# controller_board.net
KiCad netlist of a schematic drawn in EAGLE
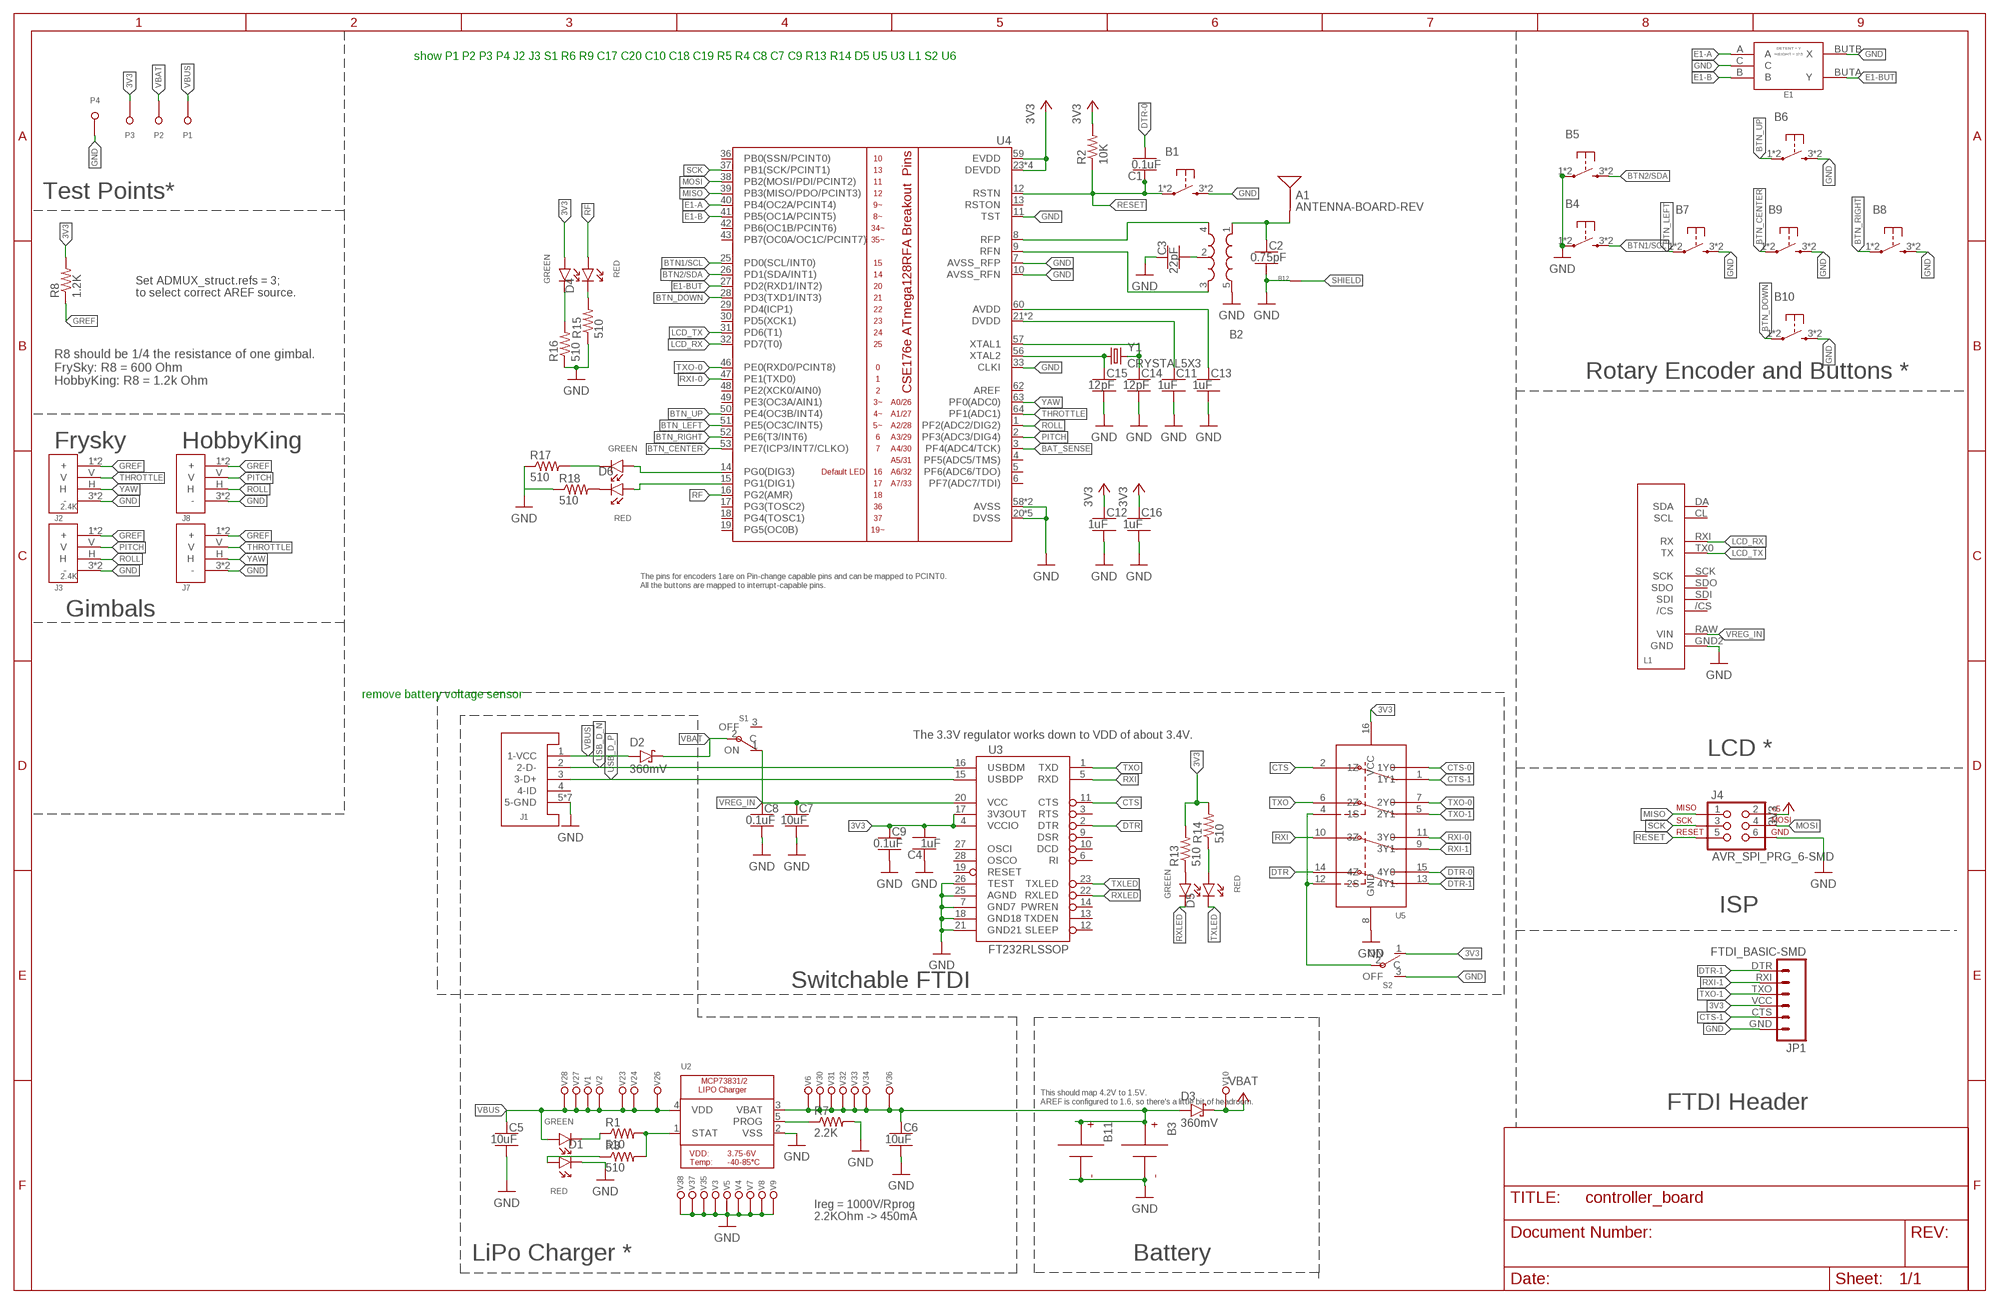
[diagram p0: schematic, sheet 1]

(export (version "E")
  (design (tool "Eeschema 10.0.6"))
  (components
    (comp (ref "A1")
      (value "ANTENNA-BOARD-REV")
      (footprint "eagle-import:ANT_PCB_2.4GHZ_NRF8001_1.6MM_1OZ_REV")
      (fields (field (name "CREATOR") "Swanson"))
      (libsource (lib "eagle-import") (part "ANTENNA-BOARD-REV"))
    )
    (comp (ref "B1")
      (value "PUSHBUTTON_-4.5X4.5")
      (footprint "eagle-import:4.5MM_TACTILE_SWITCH_TL3305AF160QG")
      (fields (field (name "CREATOR") "Swanson"))
      (libsource (lib "eagle-import") (part "PUSHBUTTON_-4.5X4.5"))
    )
    (comp (ref "B2")
      (value "BALUN0805")
      (footprint "eagle-import:BALUN")
      (fields
        (field (name "MFR") "Wurth Electronics Inc")
        (field (name "MPN") "748421245")
        (field (name "CREATOR") "Swanson")
        (field (name "REVIEWER") "Swanson")
      )
      (libsource (lib "eagle-import") (part "BALUN0805"))
    )
    (comp (ref "B3")
      (value "BATTERY-SPRING-SMD")
      (footprint "eagle-import:WIRE-TERMINAL-1X2-2.5MM-SMD-AVX-009276002021106")
      (libsource (lib "eagle-import") (part "BATTERY-SPRING-SMD"))
    )
    (comp (ref "B4")
      (value "PUSHBUTTON_-4.5X4.5")
      (footprint "eagle-import:4.5MM_TACTILE_SWITCH_TL3305AF160QG")
      (fields (field (name "CREATOR") "Swanson"))
      (libsource (lib "eagle-import") (part "PUSHBUTTON_-4.5X4.5"))
    )
    (comp (ref "B5")
      (value "PUSHBUTTON_-4.5X4.5")
      (footprint "eagle-import:4.5MM_TACTILE_SWITCH_TL3305AF160QG")
      (fields (field (name "CREATOR") "Swanson"))
      (libsource (lib "eagle-import") (part "PUSHBUTTON_-4.5X4.5"))
    )
    (comp (ref "B6")
      (value "PUSHBUTTON_-4.5X4.5")
      (footprint "eagle-import:4.5MM_TACTILE_SWITCH_TL3305AF160QG")
      (fields (field (name "CREATOR") "Swanson"))
      (libsource (lib "eagle-import") (part "PUSHBUTTON_-4.5X4.5"))
    )
    (comp (ref "B7")
      (value "PUSHBUTTON_-4.5X4.5")
      (footprint "eagle-import:4.5MM_TACTILE_SWITCH_TL3305AF160QG")
      (fields (field (name "CREATOR") "Swanson"))
      (libsource (lib "eagle-import") (part "PUSHBUTTON_-4.5X4.5"))
    )
    (comp (ref "B8")
      (value "PUSHBUTTON_-4.5X4.5")
      (footprint "eagle-import:4.5MM_TACTILE_SWITCH_TL3305AF160QG")
      (fields (field (name "CREATOR") "Swanson"))
      (libsource (lib "eagle-import") (part "PUSHBUTTON_-4.5X4.5"))
    )
    (comp (ref "B9")
      (value "PUSHBUTTON_-4.5X4.5")
      (footprint "eagle-import:4.5MM_TACTILE_SWITCH_TL3305AF160QG")
      (fields (field (name "CREATOR") "Swanson"))
      (libsource (lib "eagle-import") (part "PUSHBUTTON_-4.5X4.5"))
    )
    (comp (ref "B10")
      (value "PUSHBUTTON_-4.5X4.5")
      (footprint "eagle-import:4.5MM_TACTILE_SWITCH_TL3305AF160QG")
      (fields (field (name "CREATOR") "Swanson"))
      (libsource (lib "eagle-import") (part "PUSHBUTTON_-4.5X4.5"))
    )
    (comp (ref "B11")
      (value "BATTERY-SCREW-TERMINAL")
      (footprint "eagle-import:SCREW-TERMINAL-1X2-2.54MM")
      (fields (field (name "CREATOR") "Swanson"))
      (libsource (lib "eagle-import") (part "BATTERY-SCREW-TERMINAL"))
    )
    (comp (ref "B12")
      (value "NET_BRIDGE")
      (footprint "eagle-import:NET_BRIDGE")
      (fields (field (name "CREATOR") "Michael Gonzalez"))
      (libsource (lib "eagle-import") (part "NET_BRIDGE"))
    )
    (comp (ref "C1")
      (value "0.1uF")
      (footprint "eagle-import:CAPC2012X140_HS")
      (fields
        (field (name "MFR") "TDK")
        (field (name "MPN") "C2012X7R2A104K125AA")
        (field (name "CREATOR") "Swanson")
        (field (name "REVIEWER") "Swanson")
      )
      (libsource (lib "eagle-import") (part "CAPACITOR-NP_SMD-2012-0805_CERAMIC-0.1UF"))
    )
    (comp (ref "C2")
      (value "0.75pF")
      (footprint "eagle-import:CAPC2012X140_HS")
      (fields
        (field (name "MFR") "Murata Electronics North America")
        (field (name "MPN") "GQM2195C2AR75CB01D")
        (field (name "CREATOR") "Swanson")
        (field (name "REVIEWER") "Swanson")
      )
      (libsource (lib "eagle-import") (part "CAPACITOR-NP_SMD-2012-0805_CERAMIC-0.75PF"))
    )
    (comp (ref "C3")
      (value "22pF")
      (footprint "eagle-import:CAPC2012X140_HS")
      (fields
        (field (name "MFR") "Murata Electronics North America")
        (field (name "MPN") "GRM21A5C2E220JW01D")
        (field (name "CREATOR") "Swanson")
        (field (name "REVIEWER") "Swanson")
      )
      (libsource (lib "eagle-import") (part "CAPACITOR-NP_SMD-2012-0805_CERAMIC-22PF"))
    )
    (comp (ref "C4")
      (value "1uF")
      (footprint "eagle-import:CAPC2012X140_HS")
      (fields
        (field (name "MFR") "Taiyo Yuden")
        (field (name "MPN") "TMK212B7105KG-T")
        (field (name "CREATOR") "Swanson")
        (field (name "REVIEWER") "Swanson")
      )
      (libsource (lib "eagle-import") (part "CAPACITOR-NP_SMD-2012-0805_CERAMIC-1UF"))
    )
    (comp (ref "C5")
      (value "10uF")
      (footprint "eagle-import:CAPC2012X140_HS")
      (fields (field (name "CREATOR") "Swanson") (field (name "REVIEWER") "Swanson"))
      (libsource (lib "eagle-import") (part "CAPACITOR-NP_SMD-2012-0805_CERAMIC-10UF"))
    )
    (comp (ref "C6")
      (value "10uF")
      (footprint "eagle-import:CAPC2012X140_HS")
      (fields (field (name "CREATOR") "Swanson") (field (name "REVIEWER") "Swanson"))
      (libsource (lib "eagle-import") (part "CAPACITOR-NP_SMD-2012-0805_CERAMIC-10UF"))
    )
    (comp (ref "C7")
      (value "10uF")
      (footprint "eagle-import:CAPC2012X140_HS")
      (fields (field (name "CREATOR") "Swanson") (field (name "REVIEWER") "Swanson"))
      (libsource (lib "eagle-import") (part "CAPACITOR-NP_SMD-2012-0805_CERAMIC-10UF"))
    )
    (comp (ref "C8")
      (value "0.1uF")
      (footprint "eagle-import:CAPC2012X140_HS")
      (fields
        (field (name "MFR") "TDK")
        (field (name "MPN") "C2012X7R2A104K125AA")
        (field (name "CREATOR") "Swanson")
        (field (name "REVIEWER") "Swanson")
      )
      (libsource (lib "eagle-import") (part "CAPACITOR-NP_SMD-2012-0805_CERAMIC-0.1UF"))
    )
    (comp (ref "C9")
      (value "0.1uF")
      (footprint "eagle-import:CAPC2012X140_HS")
      (fields
        (field (name "MFR") "TDK")
        (field (name "MPN") "C2012X7R2A104K125AA")
        (field (name "CREATOR") "Swanson")
        (field (name "REVIEWER") "Swanson")
      )
      (libsource (lib "eagle-import") (part "CAPACITOR-NP_SMD-2012-0805_CERAMIC-0.1UF"))
    )
    (comp (ref "C11")
      (value "1uF")
      (footprint "eagle-import:CAPC2012X140_HS")
      (fields
        (field (name "MFR") "Taiyo Yuden")
        (field (name "MPN") "TMK212B7105KG-T")
        (field (name "CREATOR") "Swanson")
        (field (name "REVIEWER") "Swanson")
      )
      (libsource (lib "eagle-import") (part "CAPACITOR-NP_SMD-2012-0805_CERAMIC-1UF"))
    )
    (comp (ref "C12")
      (value "1uF")
      (footprint "eagle-import:CAPC2012X140_HS")
      (fields
        (field (name "MFR") "Taiyo Yuden")
        (field (name "MPN") "TMK212B7105KG-T")
        (field (name "CREATOR") "Swanson")
        (field (name "REVIEWER") "Swanson")
      )
      (libsource (lib "eagle-import") (part "CAPACITOR-NP_SMD-2012-0805_CERAMIC-1UF"))
    )
    (comp (ref "C13")
      (value "1uF")
      (footprint "eagle-import:CAPC2012X140_HS")
      (fields
        (field (name "MFR") "Taiyo Yuden")
        (field (name "MPN") "TMK212B7105KG-T")
        (field (name "CREATOR") "Swanson")
        (field (name "REVIEWER") "Swanson")
      )
      (libsource (lib "eagle-import") (part "CAPACITOR-NP_SMD-2012-0805_CERAMIC-1UF"))
    )
    (comp (ref "C14")
      (value "12pF")
      (footprint "eagle-import:CAPC2012X140_HS")
      (fields
        (field (name "MFR") "Murata Electronics North America")
        (field (name "MPN") "GRM21A5C2E120JW01D")
        (field (name "CREATOR") "Swanson")
        (field (name "REVIEWER") "Swanson")
      )
      (libsource (lib "eagle-import") (part "CAPACITOR-NP_SMD-2012-0805_CERAMIC-12PF"))
    )
    (comp (ref "C15")
      (value "12pF")
      (footprint "eagle-import:CAPC2012X140_HS")
      (fields
        (field (name "MFR") "Murata Electronics North America")
        (field (name "MPN") "GRM21A5C2E120JW01D")
        (field (name "CREATOR") "Swanson")
        (field (name "REVIEWER") "Swanson")
      )
      (libsource (lib "eagle-import") (part "CAPACITOR-NP_SMD-2012-0805_CERAMIC-12PF"))
    )
    (comp (ref "C16")
      (value "1uF")
      (footprint "eagle-import:CAPC2012X140_HS")
      (fields
        (field (name "MFR") "Taiyo Yuden")
        (field (name "MPN") "TMK212B7105KG-T")
        (field (name "CREATOR") "Swanson")
        (field (name "REVIEWER") "Swanson")
      )
      (libsource (lib "eagle-import") (part "CAPACITOR-NP_SMD-2012-0805_CERAMIC-1UF"))
    )
    (comp (ref "D1")
      (value "LED-2X-GREEN/RED")
      (footprint "eagle-import:LED-2X-LTST-C155")
      (fields
        (field (name "COLOR2") "RED")
        (field (name "COLOR1") "GREEN")
        (field (name "CREATOR") "Swanson")
      )
      (libsource (lib "eagle-import") (part "LED-2X-GREEN/RED"))
    )
    (comp (ref "D2")
      (value "360mV")
      (footprint "eagle-import:SOD3716X135_HS")
      (fields
        (field (name "MFR") "Toshiba Semiconductor and Storage")
        (field (name "MPN") "CRS08(TE85L,Q,M)")
        (field (name "CREATOR") "Swanson")
        (field (name "REVIEWER") "Swanson")
      )
      (libsource (lib "eagle-import") (part "DIODE-SCHOTTKY_SMD-SOD123-360MV"))
    )
    (comp (ref "D3")
      (value "360mV")
      (footprint "eagle-import:SOD3716X135_HS")
      (fields
        (field (name "MFR") "Toshiba Semiconductor and Storage")
        (field (name "MPN") "CRS08(TE85L,Q,M)")
        (field (name "CREATOR") "Swanson")
        (field (name "REVIEWER") "Swanson")
      )
      (libsource (lib "eagle-import") (part "DIODE-SCHOTTKY_SMD-SOD123-360MV"))
    )
    (comp (ref "D4")
      (value "LED-2X-GREEN/RED")
      (footprint "eagle-import:LED-2X-LTST-C155")
      (fields
        (field (name "COLOR2") "RED")
        (field (name "COLOR1") "GREEN")
        (field (name "CREATOR") "Swanson")
      )
      (libsource (lib "eagle-import") (part "LED-2X-GREEN/RED"))
    )
    (comp (ref "D5")
      (value "LED-2X-GREEN/RED")
      (footprint "eagle-import:LED-2X-LTST-C155")
      (fields
        (field (name "COLOR2") "RED")
        (field (name "COLOR1") "GREEN")
        (field (name "CREATOR") "Swanson")
      )
      (libsource (lib "eagle-import") (part "LED-2X-GREEN/RED"))
    )
    (comp (ref "D6")
      (value "LED-2X-GREEN/RED")
      (footprint "eagle-import:LED-2X-LTST-C155")
      (fields
        (field (name "COLOR2") "RED")
        (field (name "COLOR1") "GREEN")
        (field (name "CREATOR") "Swanson")
      )
      (libsource (lib "eagle-import") (part "LED-2X-GREEN/RED"))
    )
    (comp (ref "E1")
      (value "ROTARY-ENCODER-W/BUTTON-BOURNS-PEC12R-4217F")
      (footprint "eagle-import:BOURNS-PEC12R")
      (fields (field (name "DETENT") "Y") (field (name "HEIGHT") "17.5") (field (name "CREATOR") "Swanson"))
      (libsource (lib "eagle-import") (part "ROTARY-ENCODER-W/BUTTON-BOURNS-PEC12R-4217F"))
    )
    (comp (ref "J1")
      (value "USB-MICROA-AMPHENOL-10118192-0001LF")
      (footprint "eagle-import:USB-MICROA-10118192-0001LF")
      (fields (field (name "CREATOR") "Swanson"))
      (libsource (lib "eagle-import") (part "USB-MICROA-AMPHENOL-10118192-0001LF"))
    )
    (comp (ref "J2")
      (value "2.4K")
      (footprint "eagle-import:JST-13-PTH")
      (fields (field (name "CREATOR") "Swanson"))
      (libsource (lib "eagle-import") (part "FRSKY-GIMBAL-FRYSKY"))
    )
    (comp (ref "J3")
      (value "2.4K")
      (footprint "eagle-import:JST-13-PTH")
      (fields (field (name "SPICEPREFIX") "E") (field (name "CREATOR") "Swanson"))
      (libsource (lib "eagle-import") (part "FRSKY-GIMBAL-FRYSKY"))
    )
    (comp (ref "J4")
      (value "AVR_SPI_PRG_6-SMD")
      (footprint "eagle-import:2X3-SMD")
      (fields (field (name "CREATOR") "Swanson"))
      (libsource (lib "eagle-import") (part "AVR_SPI_PRG_6-SMD"))
    )
    (comp (ref "J7")
      (value "FRSKY-GIMBAL-2X-SERVO-SMD")
      (footprint "eagle-import:2X-SERVO-SMD")
      (libsource (lib "eagle-import") (part "FRSKY-GIMBAL-2X-SERVO-SMD"))
    )
    (comp (ref "J8")
      (value "FRSKY-GIMBAL-2X-SERVO-SMD")
      (footprint "eagle-import:2X-SERVO-SMD")
      (libsource (lib "eagle-import") (part "FRSKY-GIMBAL-2X-SERVO-SMD"))
    )
    (comp (ref "JP1")
      (value "FTDI_BASIC-SMD")
      (footprint "eagle-import:FTDI-BASIC-SMD")
      (libsource (lib "eagle-import") (part "FTDI_BASIC-SMD"))
    )
    (comp (ref "L1")
      (value "SPARKFUN_SERLCD_SERIAL_REDUCED-SMD")
      (footprint "eagle-import:SPARKFUN_SERLCD_16X2_REDUCED_SMD")
      (fields (field (name "CREATOR") "Swanson"))
      (libsource (lib "eagle-import") (part "SPARKFUN_SERLCD_SERIAL_REDUCED-SMD"))
    )
    (comp (ref "P1")
      (value "TEST-POINT")
      (footprint "eagle-import:TEST-POINT-KEYSTONE-5000")
      (fields (field (name "CREATOR") "Swanson"))
      (libsource (lib "eagle-import") (part "TEST-POINT"))
    )
    (comp (ref "P2")
      (value "TEST-POINT")
      (footprint "eagle-import:TEST-POINT-KEYSTONE-5000")
      (fields (field (name "CREATOR") "Swanson"))
      (libsource (lib "eagle-import") (part "TEST-POINT"))
    )
    (comp (ref "P3")
      (value "TEST-POINT")
      (footprint "eagle-import:TEST-POINT-KEYSTONE-5000")
      (fields (field (name "CREATOR") "Swanson"))
      (libsource (lib "eagle-import") (part "TEST-POINT"))
    )
    (comp (ref "P4")
      (value "TEST-POINT")
      (footprint "eagle-import:TEST-POINT-KEYSTONE-5000")
      (fields (field (name "CREATOR") "Swanson"))
      (libsource (lib "eagle-import") (part "TEST-POINT"))
    )
    (comp (ref "R1")
      (value "510")
      (footprint "eagle-import:RESC2012X60_HS")
      (fields (field (name "CREATOR") "SWANSON"))
      (libsource (lib "eagle-import") (part "RESISTOR_SMD-2012-0805-510"))
    )
    (comp (ref "R2")
      (value "10K")
      (footprint "eagle-import:RESC2012X60_HS")
      (fields
        (field (name "MFR") "Yageo")
        (field (name "MPN") "RC0805JR-0710KL")
        (field (name "CREATOR") "Swanson")
        (field (name "REVIEWER") "Swanson")
      )
      (libsource (lib "eagle-import") (part "RESISTOR_SMD-2012-0805-10K"))
    )
    (comp (ref "R3")
      (value "510")
      (footprint "eagle-import:RESC2012X60_HS")
      (fields (field (name "CREATOR") "SWANSON"))
      (libsource (lib "eagle-import") (part "RESISTOR_SMD-2012-0805-510"))
    )
    (comp (ref "R7")
      (value "2.2K")
      (footprint "eagle-import:RESC2012X60_HS")
      (fields (field (name "CREATOR") "SWANSON"))
      (libsource (lib "eagle-import") (part "RESISTOR_SMD-2012-0805-2.2K"))
    )
    (comp (ref "R8")
      (value "1.2K")
      (footprint "eagle-import:RESC2012X60_HS")
      (fields (field (name "CREATOR") "Swanson"))
      (libsource (lib "eagle-import") (part "RESISTOR_SMD-2012-0805-1.2K"))
    )
    (comp (ref "R13")
      (value "510")
      (footprint "eagle-import:RESC2012X60_HS")
      (fields (field (name "CREATOR") "SWANSON"))
      (libsource (lib "eagle-import") (part "RESISTOR_SMD-2012-0805-510"))
    )
    (comp (ref "R14")
      (value "510")
      (footprint "eagle-import:RESC2012X60_HS")
      (fields (field (name "CREATOR") "SWANSON"))
      (libsource (lib "eagle-import") (part "RESISTOR_SMD-2012-0805-510"))
    )
    (comp (ref "R15")
      (value "510")
      (footprint "eagle-import:RESC2012X60_HS")
      (fields (field (name "CREATOR") "SWANSON"))
      (libsource (lib "eagle-import") (part "RESISTOR_SMD-2012-0805-510"))
    )
    (comp (ref "R16")
      (value "510")
      (footprint "eagle-import:RESC2012X60_HS")
      (fields (field (name "CREATOR") "SWANSON"))
      (libsource (lib "eagle-import") (part "RESISTOR_SMD-2012-0805-510"))
    )
    (comp (ref "R17")
      (value "510")
      (footprint "eagle-import:RESC2012X60_HS")
      (fields (field (name "CREATOR") "SWANSON"))
      (libsource (lib "eagle-import") (part "RESISTOR_SMD-2012-0805-510"))
    )
    (comp (ref "R18")
      (value "510")
      (footprint "eagle-import:RESC2012X60_HS")
      (fields (field (name "CREATOR") "SWANSON"))
      (libsource (lib "eagle-import") (part "RESISTOR_SMD-2012-0805-510"))
    )
    (comp (ref "S1")
      (value "POWER-SWITCH-MFS201N-9-Z-SMD-VERTICAL")
      (footprint "eagle-import:JS102011JCQN")
      (fields (field (name "CREATOR") "Swanson"))
      (libsource (lib "eagle-import") (part "POWER-SWITCH-MFS201N-9-Z-SMD-VERTICAL"))
    )
    (comp (ref "S2")
      (value "POWER-SWITCH-MFS201N-9-Z-SMD-VERTICAL")
      (footprint "eagle-import:JS102011JCQN")
      (fields (field (name "CREATOR") "Swanson"))
      (libsource (lib "eagle-import") (part "POWER-SWITCH-MFS201N-9-Z-SMD-VERTICAL"))
    )
    (comp (ref "U2")
      (value "MCP73831T-2ACI/OT")
      (footprint "eagle-import:SOT23-5")
      (fields (field (name "CREATOR") "Adafruit"))
      (libsource (lib "eagle-import") (part "MCP73831/2"))
    )
    (comp (ref "U3")
      (value "FT232RLSSOP")
      (footprint "eagle-import:SSOP28DB")
      (fields (field (name "CREATOR") "Swanson"))
      (libsource (lib "eagle-import") (part "FT232RLSSOP"))
    )
    (comp (ref "U4")
      (value "ATMEGA128RFA1")
      (footprint "eagle-import:QFN-64")
      (fields
        (field (name "MFR") "Atmel")
        (field (name "MPN") "ATMEGA128RFA1-ZUR00")
        (field (name "CREATOR") "Swanson")
        (field (name "REVIEWER") "Swanson")
      )
      (libsource (lib "eagle-import") (part "ATMEGA128RFA1"))
    )
    (comp (ref "U5")
      (value "DPDT-X2")
      (footprint "eagle-import:SOP65P640X110-16")
      (fields (field (name "CREATOR") "Swanson"))
      (libsource (lib "eagle-import") (part "DPDT-X2"))
    )
    (comp (ref "V1")
      (value "LOCKED-VIA-0.2")
      (footprint "eagle-import:VIA-0.2MM")
      (fields (field (name "CREATOR") "Swanson"))
      (libsource (lib "eagle-import") (part "LOCKED-VIA-0.2"))
    )
    (comp (ref "V2")
      (value "LOCKED-VIA-0.2")
      (footprint "eagle-import:VIA-0.2MM")
      (fields (field (name "CREATOR") "Swanson"))
      (libsource (lib "eagle-import") (part "LOCKED-VIA-0.2"))
    )
    (comp (ref "V3")
      (value "LOCKED-VIA-0.2")
      (footprint "eagle-import:VIA-0.2MM")
      (fields (field (name "CREATOR") "Swanson"))
      (libsource (lib "eagle-import") (part "LOCKED-VIA-0.2"))
    )
    (comp (ref "V4")
      (value "LOCKED-VIA-0.2")
      (footprint "eagle-import:VIA-0.2MM")
      (fields (field (name "CREATOR") "Swanson"))
      (libsource (lib "eagle-import") (part "LOCKED-VIA-0.2"))
    )
    (comp (ref "V5")
      (value "LOCKED-VIA-0.2")
      (footprint "eagle-import:VIA-0.2MM")
      (fields (field (name "CREATOR") "Swanson"))
      (libsource (lib "eagle-import") (part "LOCKED-VIA-0.2"))
    )
    (comp (ref "V6")
      (value "LOCKED-VIA-0.2")
      (footprint "eagle-import:VIA-0.2MM")
      (fields (field (name "CREATOR") "Swanson"))
      (libsource (lib "eagle-import") (part "LOCKED-VIA-0.2"))
    )
    (comp (ref "V7")
      (value "LOCKED-VIA-0.2")
      (footprint "eagle-import:VIA-0.2MM")
      (fields (field (name "CREATOR") "Swanson"))
      (libsource (lib "eagle-import") (part "LOCKED-VIA-0.2"))
    )
    (comp (ref "V8")
      (value "LOCKED-VIA-0.2")
      (footprint "eagle-import:VIA-0.2MM")
      (fields (field (name "CREATOR") "Swanson"))
      (libsource (lib "eagle-import") (part "LOCKED-VIA-0.2"))
    )
    (comp (ref "V9")
      (value "LOCKED-VIA-0.2")
      (footprint "eagle-import:VIA-0.2MM")
      (fields (field (name "CREATOR") "Swanson"))
      (libsource (lib "eagle-import") (part "LOCKED-VIA-0.2"))
    )
    (comp (ref "V10")
      (value "LOCKED-VIA-0.2")
      (footprint "eagle-import:VIA-0.2MM")
      (fields (field (name "CREATOR") "Swanson"))
      (libsource (lib "eagle-import") (part "LOCKED-VIA-0.2"))
    )
    (comp (ref "V23")
      (value "LOCKED-VIA-0.2")
      (footprint "eagle-import:VIA-0.2MM")
      (fields (field (name "CREATOR") "Swanson"))
      (libsource (lib "eagle-import") (part "LOCKED-VIA-0.2"))
    )
    (comp (ref "V24")
      (value "LOCKED-VIA-0.2")
      (footprint "eagle-import:VIA-0.2MM")
      (fields (field (name "CREATOR") "Swanson"))
      (libsource (lib "eagle-import") (part "LOCKED-VIA-0.2"))
    )
    (comp (ref "V26")
      (value "LOCKED-VIA-0.2")
      (footprint "eagle-import:VIA-0.2MM")
      (fields (field (name "CREATOR") "Swanson"))
      (libsource (lib "eagle-import") (part "LOCKED-VIA-0.2"))
    )
    (comp (ref "V27")
      (value "LOCKED-VIA-0.2")
      (footprint "eagle-import:VIA-0.2MM")
      (fields (field (name "CREATOR") "Swanson"))
      (libsource (lib "eagle-import") (part "LOCKED-VIA-0.2"))
    )
    (comp (ref "V28")
      (value "LOCKED-VIA-0.2")
      (footprint "eagle-import:VIA-0.2MM")
      (fields (field (name "CREATOR") "Swanson"))
      (libsource (lib "eagle-import") (part "LOCKED-VIA-0.2"))
    )
    (comp (ref "V30")
      (value "LOCKED-VIA-0.2")
      (footprint "eagle-import:VIA-0.2MM")
      (fields (field (name "CREATOR") "Swanson"))
      (libsource (lib "eagle-import") (part "LOCKED-VIA-0.2"))
    )
    (comp (ref "V31")
      (value "LOCKED-VIA-0.2")
      (footprint "eagle-import:VIA-0.2MM")
      (fields (field (name "CREATOR") "Swanson"))
      (libsource (lib "eagle-import") (part "LOCKED-VIA-0.2"))
    )
    (comp (ref "V32")
      (value "LOCKED-VIA-0.2")
      (footprint "eagle-import:VIA-0.2MM")
      (fields (field (name "CREATOR") "Swanson"))
      (libsource (lib "eagle-import") (part "LOCKED-VIA-0.2"))
    )
    (comp (ref "V33")
      (value "LOCKED-VIA-0.2")
      (footprint "eagle-import:VIA-0.2MM")
      (fields (field (name "CREATOR") "Swanson"))
      (libsource (lib "eagle-import") (part "LOCKED-VIA-0.2"))
    )
    (comp (ref "V34")
      (value "LOCKED-VIA-0.2")
      (footprint "eagle-import:VIA-0.2MM")
      (fields (field (name "CREATOR") "Swanson"))
      (libsource (lib "eagle-import") (part "LOCKED-VIA-0.2"))
    )
    (comp (ref "V35")
      (value "LOCKED-VIA-0.2")
      (footprint "eagle-import:VIA-0.2MM")
      (fields (field (name "CREATOR") "Swanson"))
      (libsource (lib "eagle-import") (part "LOCKED-VIA-0.2"))
    )
    (comp (ref "V36")
      (value "LOCKED-VIA-0.2")
      (footprint "eagle-import:VIA-0.2MM")
      (fields (field (name "CREATOR") "Swanson"))
      (libsource (lib "eagle-import") (part "LOCKED-VIA-0.2"))
    )
    (comp (ref "V37")
      (value "LOCKED-VIA-0.2")
      (footprint "eagle-import:VIA-0.2MM")
      (fields (field (name "CREATOR") "Swanson"))
      (libsource (lib "eagle-import") (part "LOCKED-VIA-0.2"))
    )
    (comp (ref "V38")
      (value "LOCKED-VIA-0.2")
      (footprint "eagle-import:VIA-0.2MM")
      (fields (field (name "CREATOR") "Swanson"))
      (libsource (lib "eagle-import") (part "LOCKED-VIA-0.2"))
    )
    (comp (ref "Y1")
      (value "CRYSTAL5X3")
      (footprint "eagle-import:CRYSTAL-SMD-5X3")
      (fields
        (field (name "MFR") "Abracon LLC")
        (field (name "MPN") "ABM3B-16.000MHZ-B2-T")
        (field (name "CREATOR") "Swanson")
        (field (name "REVIEWER") "Swanson")
      )
      (libsource (lib "eagle-import") (part "CRYSTAL5X3"))
    )
  )
  (nets
    (net (code "1") (name "3V3") (class "Default")
      (node (ref "C12") (pin "1") (pinfunction "1_1") (pintype "passive"))
      (node (ref "C16") (pin "1") (pinfunction "1_1") (pintype "passive"))
      (node (ref "C4") (pin "2") (pinfunction "2_2") (pintype "passive"))
      (node (ref "C9") (pin "1") (pinfunction "1_1") (pintype "passive"))
      (node (ref "D4") (pin "A2") (pinfunction "A2_A2") (pintype "passive"))
      (node (ref "J4") (pin "2") (pinfunction "2_2") (pintype "passive"))
      (node (ref "JP1") (pin "VCC") (pinfunction "4_VCC") (pintype "passive"))
      (node (ref "P3") (pin "T") (pinfunction "T_T") (pintype "bidirectional"))
      (node (ref "R13") (pin "2") (pinfunction "2_2") (pintype "passive"))
      (node (ref "R14") (pin "2") (pinfunction "2_2") (pintype "passive"))
      (node (ref "R2") (pin "2") (pinfunction "2_2") (pintype "passive"))
      (node (ref "R8") (pin "2") (pinfunction "2_2") (pintype "passive"))
      (node (ref "S2") (pin "1") (pinfunction "ON_1") (pintype "bidirectional"))
      (node (ref "U3") (pin "17") (pinfunction "3V3OUT_17") (pintype "output"))
      (node (ref "U3") (pin "4") (pinfunction "VCCIO_4") (pintype "power_in"))
      (node (ref "U4") (pin "23") (pinfunction "DEVDD_23") (pintype "bidirectional"))
      (node (ref "U4") (pin "34") (pinfunction "DEVDD_34") (pintype "bidirectional"))
      (node (ref "U4") (pin "44") (pinfunction "DEVDD_44") (pintype "bidirectional"))
      (node (ref "U4") (pin "54") (pinfunction "DEVDD_54") (pintype "bidirectional"))
      (node (ref "U4") (pin "59") (pinfunction "EVDD_59") (pintype "bidirectional"))
      (node (ref "U5") (pin "16") (pinfunction "VCC_16") (pintype "bidirectional"))
    )
    (net (code "2") (name "BAT_SENSE") (class "Default")
      (node (ref "U4") (pin "3") (pinfunction "PF4(ADC4/TCK)_3") (pintype "bidirectional"))
    )
    (net (code "3") (name "BTN1{slash}SCL") (class "Default")
      (node (ref "B4") (pin "3") (pinfunction "2_3") (pintype "passive"))
      (node (ref "B4") (pin "4") (pinfunction "2_4") (pintype "passive"))
      (node (ref "U4") (pin "25") (pinfunction "PD0(SCL/INT0)_25") (pintype "bidirectional"))
    )
    (net (code "4") (name "BTN2{slash}SDA") (class "Default")
      (node (ref "B5") (pin "3") (pinfunction "2_3") (pintype "passive"))
      (node (ref "B5") (pin "4") (pinfunction "2_4") (pintype "passive"))
      (node (ref "U4") (pin "26") (pinfunction "PD1(SDA/INT1)_26") (pintype "bidirectional"))
    )
    (net (code "5") (name "BTN_CENTER") (class "Default")
      (node (ref "B9") (pin "1") (pinfunction "1_1") (pintype "passive"))
      (node (ref "B9") (pin "2") (pinfunction "1_2") (pintype "passive"))
      (node (ref "U4") (pin "53") (pinfunction "PE7(ICP3/INT7/CLKO)_53") (pintype "bidirectional"))
    )
    (net (code "6") (name "BTN_DOWN") (class "Default")
      (node (ref "B10") (pin "1") (pinfunction "1_1") (pintype "passive"))
      (node (ref "B10") (pin "2") (pinfunction "1_2") (pintype "passive"))
      (node (ref "U4") (pin "28") (pinfunction "PD3(TXD1/INT3)_28") (pintype "bidirectional"))
    )
    (net (code "7") (name "BTN_LEFT") (class "Default")
      (node (ref "B7") (pin "1") (pinfunction "1_1") (pintype "passive"))
      (node (ref "B7") (pin "2") (pinfunction "1_2") (pintype "passive"))
      (node (ref "U4") (pin "51") (pinfunction "PE5(OC3C/INT5)_51") (pintype "bidirectional"))
    )
    (net (code "8") (name "BTN_RIGHT") (class "Default")
      (node (ref "B8") (pin "1") (pinfunction "1_1") (pintype "passive"))
      (node (ref "B8") (pin "2") (pinfunction "1_2") (pintype "passive"))
      (node (ref "U4") (pin "52") (pinfunction "PE6(T3/INT6)_52") (pintype "bidirectional"))
    )
    (net (code "9") (name "BTN_UP") (class "Default")
      (node (ref "B6") (pin "1") (pinfunction "1_1") (pintype "passive"))
      (node (ref "B6") (pin "2") (pinfunction "1_2") (pintype "passive"))
      (node (ref "U4") (pin "50") (pinfunction "PE4(OC3B/INT4)_50") (pintype "bidirectional"))
    )
    (net (code "10") (name "CTS") (class "Default")
      (node (ref "U3") (pin "11") (pinfunction "CTS_11") (pintype "input"))
      (node (ref "U5") (pin "2") (pinfunction "1Z_2") (pintype "bidirectional"))
    )
    (net (code "11") (name "CTS-0") (class "Default")
      (node (ref "U5") (pin "3") (pinfunction "1Y0_3") (pintype "bidirectional"))
    )
    (net (code "12") (name "CTS-1") (class "Default")
      (node (ref "JP1") (pin "CTS") (pinfunction "5_CTS") (pintype "passive"))
      (node (ref "U5") (pin "1") (pinfunction "1Y1_1") (pintype "bidirectional"))
    )
    (net (code "13") (name "DTR") (class "Default")
      (node (ref "U3") (pin "2") (pinfunction "DTR_2") (pintype "output"))
      (node (ref "U5") (pin "14") (pinfunction "4Z_14") (pintype "bidirectional"))
    )
    (net (code "14") (name "DTR-0") (class "Default")
      (node (ref "C1") (pin "2") (pinfunction "2_2") (pintype "passive"))
      (node (ref "U5") (pin "15") (pinfunction "4Y0_15") (pintype "bidirectional"))
    )
    (net (code "15") (name "DTR-1") (class "Default")
      (node (ref "JP1") (pin "DTR") (pinfunction "1_DTR") (pintype "passive"))
      (node (ref "U5") (pin "13") (pinfunction "4Y1_13") (pintype "bidirectional"))
    )
    (net (code "16") (name "E1-A") (class "Default")
      (node (ref "E1") (pin "A") (pinfunction "A_A") (pintype "bidirectional"))
      (node (ref "U4") (pin "40") (pinfunction "PB4(OC2A/PCINT4)_40") (pintype "bidirectional"))
    )
    (net (code "17") (name "E1-B") (class "Default")
      (node (ref "E1") (pin "B") (pinfunction "B_B") (pintype "bidirectional"))
      (node (ref "U4") (pin "41") (pinfunction "PB5(OC1A/PCINT5)_41") (pintype "bidirectional"))
    )
    (net (code "18") (name "E1-BUT") (class "Default")
      (node (ref "E1") (pin "BUTA") (pinfunction "Y_BUTA") (pintype "bidirectional"))
      (node (ref "U4") (pin "27") (pinfunction "PD2(RXD1/INT2)_27") (pintype "bidirectional"))
    )
    (net (code "19") (name "GND") (class "Default")
      (node (ref "B1") (pin "3") (pinfunction "2_3") (pintype "passive"))
      (node (ref "B1") (pin "4") (pinfunction "2_4") (pintype "passive"))
      (node (ref "B10") (pin "3") (pinfunction "2_3") (pintype "passive"))
      (node (ref "B10") (pin "4") (pinfunction "2_4") (pintype "passive"))
      (node (ref "B11") (pin "1") (pinfunction "N_1") (pintype "bidirectional"))
      (node (ref "B12") (pin "P1") (pinfunction "P1_P1") (pintype "bidirectional"))
      (node (ref "B2") (pin "5") (pinfunction "GND_5") (pintype "bidirectional"))
      (node (ref "B3") (pin "2A") (pinfunction "N_2A") (pintype "bidirectional"))
      (node (ref "B3") (pin "2B") (pinfunction "N_2B") (pintype "bidirectional"))
      (node (ref "B4") (pin "1") (pinfunction "1_1") (pintype "passive"))
      (node (ref "B4") (pin "2") (pinfunction "1_2") (pintype "passive"))
      (node (ref "B5") (pin "1") (pinfunction "1_1") (pintype "passive"))
      (node (ref "B5") (pin "2") (pinfunction "1_2") (pintype "passive"))
      (node (ref "B6") (pin "3") (pinfunction "2_3") (pintype "passive"))
      (node (ref "B6") (pin "4") (pinfunction "2_4") (pintype "passive"))
      (node (ref "B7") (pin "3") (pinfunction "2_3") (pintype "passive"))
      (node (ref "B7") (pin "4") (pinfunction "2_4") (pintype "passive"))
      (node (ref "B8") (pin "3") (pinfunction "2_3") (pintype "passive"))
      (node (ref "B8") (pin "4") (pinfunction "2_4") (pintype "passive"))
      (node (ref "B9") (pin "3") (pinfunction "2_3") (pintype "passive"))
      (node (ref "B9") (pin "4") (pinfunction "2_4") (pintype "passive"))
      (node (ref "C11") (pin "2") (pinfunction "2_2") (pintype "passive"))
      (node (ref "C12") (pin "2") (pinfunction "2_2") (pintype "passive"))
      (node (ref "C13") (pin "2") (pinfunction "2_2") (pintype "passive"))
      (node (ref "C14") (pin "2") (pinfunction "2_2") (pintype "passive"))
      (node (ref "C15") (pin "2") (pinfunction "2_2") (pintype "passive"))
      (node (ref "C16") (pin "2") (pinfunction "2_2") (pintype "passive"))
      (node (ref "C2") (pin "2") (pinfunction "2_2") (pintype "passive"))
      (node (ref "C3") (pin "1") (pinfunction "1_1") (pintype "passive"))
      (node (ref "C4") (pin "1") (pinfunction "1_1") (pintype "passive"))
      (node (ref "C5") (pin "2") (pinfunction "2_2") (pintype "passive"))
      (node (ref "C6") (pin "2") (pinfunction "2_2") (pintype "passive"))
      (node (ref "C7") (pin "2") (pinfunction "2_2") (pintype "passive"))
      (node (ref "C8") (pin "2") (pinfunction "2_2") (pintype "passive"))
      (node (ref "C9") (pin "2") (pinfunction "2_2") (pintype "passive"))
      (node (ref "D1") (pin "C1") (pinfunction "C1_C1") (pintype "passive"))
      (node (ref "E1") (pin "BUTB") (pinfunction "X_BUTB") (pintype "bidirectional"))
      (node (ref "E1") (pin "C") (pinfunction "C_C") (pintype "bidirectional"))
      (node (ref "J1") (pin "10") (pinfunction "5-GND_10") (pintype "bidirectional"))
      (node (ref "J1") (pin "11") (pinfunction "5-GND_11") (pintype "bidirectional"))
      (node (ref "J1") (pin "5") (pinfunction "5-GND_5") (pintype "bidirectional"))
      (node (ref "J1") (pin "6") (pinfunction "5-GND_6") (pintype "bidirectional"))
      (node (ref "J1") (pin "7") (pinfunction "5-GND_7") (pintype "bidirectional"))
      (node (ref "J1") (pin "8") (pinfunction "5-GND_8") (pintype "bidirectional"))
      (node (ref "J1") (pin "9") (pinfunction "5-GND_9") (pintype "bidirectional"))
      (node (ref "J2") (pin "3") (pinfunction "-_3") (pintype "bidirectional"))
      (node (ref "J2") (pin "6") (pinfunction "-_6") (pintype "bidirectional"))
      (node (ref "J3") (pin "3") (pinfunction "-_3") (pintype "bidirectional"))
      (node (ref "J3") (pin "6") (pinfunction "-_6") (pintype "bidirectional"))
      (node (ref "J4") (pin "6") (pinfunction "6_6") (pintype "passive"))
      (node (ref "J7") (pin "3") (pinfunction "-_3") (pintype "bidirectional"))
      (node (ref "J7") (pin "6") (pinfunction "-_6") (pintype "bidirectional"))
      (node (ref "J8") (pin "3") (pinfunction "-_3") (pintype "bidirectional"))
      (node (ref "J8") (pin "6") (pinfunction "-_6") (pintype "bidirectional"))
      (node (ref "JP1") (pin "GND") (pinfunction "6_GND") (pintype "passive"))
      (node (ref "L1") (pin "GND2") (pinfunction "GND_GND2") (pintype "bidirectional"))
      (node (ref "P4") (pin "T") (pinfunction "T_T") (pintype "bidirectional"))
      (node (ref "R15") (pin "1") (pinfunction "1_1") (pintype "passive"))
      (node (ref "R16") (pin "1") (pinfunction "1_1") (pintype "passive"))
      (node (ref "R17") (pin "1") (pinfunction "1_1") (pintype "passive"))
      (node (ref "R18") (pin "1") (pinfunction "1_1") (pintype "passive"))
      (node (ref "R7") (pin "2") (pinfunction "2_2") (pintype "passive"))
      (node (ref "S2") (pin "3") (pinfunction "OFF_3") (pintype "bidirectional"))
      (node (ref "U2") (pin "2") (pinfunction "VSS_2") (pintype "power_in"))
      (node (ref "U3") (pin "18") (pinfunction "GND18_18") (pintype "power_in"))
      (node (ref "U3") (pin "21") (pinfunction "GND21_21") (pintype "power_in"))
      (node (ref "U3") (pin "25") (pinfunction "AGND_25") (pintype "power_in"))
      (node (ref "U3") (pin "26") (pinfunction "TEST_26") (pintype "input"))
      (node (ref "U3") (pin "7") (pinfunction "GND7_7") (pintype "power_in"))
      (node (ref "U4") (pin "10") (pinfunction "AVSS_RFN_10") (pintype "bidirectional"))
      (node (ref "U4") (pin "11") (pinfunction "TST_11") (pintype "bidirectional"))
      (node (ref "U4") (pin "20") (pinfunction "DVSS_20") (pintype "bidirectional"))
      (node (ref "U4") (pin "24") (pinfunction "DVSS_24") (pintype "bidirectional"))
      (node (ref "U4") (pin "33") (pinfunction "CLKI_33") (pintype "bidirectional"))
      (node (ref "U4") (pin "35") (pinfunction "DVSS_35") (pintype "bidirectional"))
      (node (ref "U4") (pin "45") (pinfunction "DVSS_45") (pintype "bidirectional"))
      (node (ref "U4") (pin "55") (pinfunction "DVSS_55") (pintype "bidirectional"))
      (node (ref "U4") (pin "58") (pinfunction "AVSS_58") (pintype "bidirectional"))
      (node (ref "U4") (pin "61") (pinfunction "AVSS_61") (pintype "bidirectional"))
      (node (ref "U4") (pin "7") (pinfunction "AVSS_RFP_7") (pintype "bidirectional"))
      (node (ref "U5") (pin "8") (pinfunction "GND_8") (pintype "bidirectional"))
      (node (ref "V3") (pin "P1") (pinfunction "N_P1") (pintype "bidirectional"))
      (node (ref "V35") (pin "P1") (pinfunction "N_P1") (pintype "bidirectional"))
      (node (ref "V37") (pin "P1") (pinfunction "N_P1") (pintype "bidirectional"))
      (node (ref "V38") (pin "P1") (pinfunction "N_P1") (pintype "bidirectional"))
      (node (ref "V4") (pin "P1") (pinfunction "N_P1") (pintype "bidirectional"))
      (node (ref "V5") (pin "P1") (pinfunction "N_P1") (pintype "bidirectional"))
      (node (ref "V7") (pin "P1") (pinfunction "N_P1") (pintype "bidirectional"))
      (node (ref "V8") (pin "P1") (pinfunction "N_P1") (pintype "bidirectional"))
      (node (ref "V9") (pin "P1") (pinfunction "N_P1") (pintype "bidirectional"))
    )
    (net (code "20") (name "GREF") (class "Default")
      (node (ref "J2") (pin "1") (pinfunction "+_1") (pintype "bidirectional"))
      (node (ref "J2") (pin "4") (pinfunction "+_4") (pintype "bidirectional"))
      (node (ref "J3") (pin "1") (pinfunction "+_1") (pintype "bidirectional"))
      (node (ref "J3") (pin "4") (pinfunction "+_4") (pintype "bidirectional"))
      (node (ref "J7") (pin "1") (pinfunction "+_1") (pintype "bidirectional"))
      (node (ref "J7") (pin "4") (pinfunction "+_4") (pintype "bidirectional"))
      (node (ref "J8") (pin "1") (pinfunction "+_1") (pintype "bidirectional"))
      (node (ref "J8") (pin "4") (pinfunction "+_4") (pintype "bidirectional"))
      (node (ref "R8") (pin "1") (pinfunction "1_1") (pintype "passive"))
    )
    (net (code "21") (name "LCD_RX") (class "Default")
      (node (ref "L1") (pin "RXI") (pinfunction "RX_RXI") (pintype "bidirectional"))
      (node (ref "U4") (pin "32") (pinfunction "PD7(T0)_32") (pintype "bidirectional"))
    )
    (net (code "22") (name "LCD_TX") (class "Default")
      (node (ref "L1") (pin "TX0") (pinfunction "TX_TX0") (pintype "bidirectional"))
      (node (ref "U4") (pin "31") (pinfunction "PD6(T1)_31") (pintype "bidirectional"))
    )
    (net (code "23") (name "MISO") (class "Default")
      (node (ref "J4") (pin "1") (pinfunction "1_1") (pintype "passive"))
      (node (ref "U4") (pin "39") (pinfunction "PB3(MISO/PDO/PCINT3)_39") (pintype "bidirectional"))
    )
    (net (code "24") (name "MOSI") (class "Default")
      (node (ref "J4") (pin "4") (pinfunction "4_4") (pintype "passive"))
      (node (ref "U4") (pin "38") (pinfunction "PB2(MOSI/PDI/PCINT2)_38") (pintype "bidirectional"))
    )
    (net (code "25") (name "Net-(A1-SIGNAL)") (class "Default")
      (node (ref "A1") (pin "FEED") (pinfunction "SIGNAL_FEED") (pintype "bidirectional"))
      (node (ref "B2") (pin "1") (pinfunction "IN_1") (pintype "bidirectional"))
      (node (ref "C2") (pin "1") (pinfunction "1_1") (pintype "passive"))
    )
    (net (code "26") (name "Net-(B2-GND-Pad2)") (class "Default")
      (node (ref "B2") (pin "2") (pinfunction "GND_2") (pintype "bidirectional"))
      (node (ref "C3") (pin "2") (pinfunction "2_2") (pintype "passive"))
    )
    (net (code "27") (name "Net-(B2-OUT1)") (class "Default")
      (node (ref "B2") (pin "4") (pinfunction "OUT1_4") (pintype "bidirectional"))
      (node (ref "U4") (pin "8") (pinfunction "RFP_8") (pintype "bidirectional"))
    )
    (net (code "28") (name "Net-(B2-OUT2)") (class "Default")
      (node (ref "B2") (pin "3") (pinfunction "OUT2_3") (pintype "bidirectional"))
      (node (ref "U4") (pin "9") (pinfunction "RFN_9") (pintype "bidirectional"))
    )
    (net (code "29") (name "Net-(B11-P)") (class "Default")
      (node (ref "B11") (pin "2") (pinfunction "P_2") (pintype "bidirectional"))
      (node (ref "B3") (pin "1A") (pinfunction "P_1A") (pintype "bidirectional"))
      (node (ref "B3") (pin "1B") (pinfunction "P_1B") (pintype "bidirectional"))
      (node (ref "C6") (pin "1") (pinfunction "1_1") (pintype "passive"))
      (node (ref "D3") (pin "A") (pinfunction "A_A") (pintype "passive"))
      (node (ref "U2") (pin "3") (pinfunction "VBAT_3") (pintype "power_in"))
      (node (ref "V30") (pin "P1") (pinfunction "N_P1") (pintype "bidirectional"))
      (node (ref "V31") (pin "P1") (pinfunction "N_P1") (pintype "bidirectional"))
      (node (ref "V32") (pin "P1") (pinfunction "N_P1") (pintype "bidirectional"))
      (node (ref "V33") (pin "P1") (pinfunction "N_P1") (pintype "bidirectional"))
      (node (ref "V34") (pin "P1") (pinfunction "N_P1") (pintype "bidirectional"))
      (node (ref "V36") (pin "P1") (pinfunction "N_P1") (pintype "bidirectional"))
      (node (ref "V6") (pin "P1") (pinfunction "N_P1") (pintype "bidirectional"))
    )
    (net (code "30") (name "Net-(C11-Pad1)") (class "Default")
      (node (ref "C11") (pin "1") (pinfunction "1_1") (pintype "passive"))
      (node (ref "U4") (pin "21") (pinfunction "DVDD_21") (pintype "bidirectional"))
      (node (ref "U4") (pin "22") (pinfunction "DVDD_22") (pintype "bidirectional"))
    )
    (net (code "31") (name "Net-(D1-PadA1)") (class "Default")
      (node (ref "D1") (pin "A1") (pinfunction "A1_A1") (pintype "passive"))
      (node (ref "R3") (pin "1") (pinfunction "1_1") (pintype "passive"))
    )
    (net (code "32") (name "Net-(D1-PadC2)") (class "Default")
      (node (ref "D1") (pin "C2") (pinfunction "C2_C2") (pintype "passive"))
      (node (ref "R1") (pin "1") (pinfunction "1_1") (pintype "passive"))
    )
    (net (code "33") (name "Net-(D4-PadC1)") (class "Default")
      (node (ref "D4") (pin "C1") (pinfunction "C1_C1") (pintype "passive"))
      (node (ref "R15") (pin "2") (pinfunction "2_2") (pintype "passive"))
    )
    (net (code "34") (name "Net-(D4-PadC2)") (class "Default")
      (node (ref "D4") (pin "C2") (pinfunction "C2_C2") (pintype "passive"))
      (node (ref "R16") (pin "2") (pinfunction "2_2") (pintype "passive"))
    )
    (net (code "35") (name "Net-(D5-PadA1)") (class "Default")
      (node (ref "D5") (pin "A1") (pinfunction "A1_A1") (pintype "passive"))
      (node (ref "R14") (pin "1") (pinfunction "1_1") (pintype "passive"))
    )
    (net (code "36") (name "Net-(D5-PadA2)") (class "Default")
      (node (ref "D5") (pin "A2") (pinfunction "A2_A2") (pintype "passive"))
      (node (ref "R13") (pin "1") (pinfunction "1_1") (pintype "passive"))
    )
    (net (code "37") (name "Net-(D6-PadC1)") (class "Default")
      (node (ref "D6") (pin "C1") (pinfunction "C1_C1") (pintype "passive"))
      (node (ref "R18") (pin "2") (pinfunction "2_2") (pintype "passive"))
    )
    (net (code "38") (name "Net-(D6-PadC2)") (class "Default")
      (node (ref "D6") (pin "C2") (pinfunction "C2_C2") (pintype "passive"))
      (node (ref "R17") (pin "2") (pinfunction "2_2") (pintype "passive"))
    )
    (net (code "39") (name "Net-(S2-C)") (class "Default")
      (node (ref "S2") (pin "2") (pinfunction "C_2") (pintype "bidirectional"))
      (node (ref "U5") (pin "12") (pinfunction "2S_12") (pintype "bidirectional"))
      (node (ref "U5") (pin "4") (pinfunction "1S_4") (pintype "bidirectional"))
    )
    (net (code "40") (name "Net-(U2-PROG)") (class "Default")
      (node (ref "R7") (pin "1") (pinfunction "1_1") (pintype "passive"))
      (node (ref "U2") (pin "5") (pinfunction "PROG_5") (pintype "input"))
    )
    (net (code "41") (name "Net-(U2-STAT)") (class "Default")
      (node (ref "R1") (pin "2") (pinfunction "2_2") (pintype "passive"))
      (node (ref "R3") (pin "2") (pinfunction "2_2") (pintype "passive"))
      (node (ref "U2") (pin "1") (pinfunction "STAT_1") (pintype "output"))
    )
    (net (code "42") (name "Net-(U4-AVDD)") (class "Default")
      (node (ref "C13") (pin "1") (pinfunction "1_1") (pintype "passive"))
      (node (ref "U4") (pin "60") (pinfunction "AVDD_60") (pintype "bidirectional"))
    )
    (net (code "43") (name "Net-(U4-PG0(DIG3))") (class "Default")
      (node (ref "D6") (pin "A2") (pinfunction "A2_A2") (pintype "passive"))
      (node (ref "U4") (pin "14") (pinfunction "PG0(DIG3)_14") (pintype "bidirectional"))
    )
    (net (code "44") (name "Net-(U4-PG1(DIG1))") (class "Default")
      (node (ref "D6") (pin "A1") (pinfunction "A1_A1") (pintype "passive"))
      (node (ref "U4") (pin "15") (pinfunction "PG1(DIG1)_15") (pintype "bidirectional"))
    )
    (net (code "45") (name "Net-(U4-XTAL1)") (class "Default")
      (node (ref "C14") (pin "1") (pinfunction "1_1") (pintype "passive"))
      (node (ref "U4") (pin "57") (pinfunction "XTAL1_57") (pintype "bidirectional"))
      (node (ref "Y1") (pin "3") (pinfunction "2_3") (pintype "passive"))
    )
    (net (code "46") (name "Net-(U4-XTAL2)") (class "Default")
      (node (ref "C15") (pin "1") (pinfunction "1_1") (pintype "passive"))
      (node (ref "U4") (pin "56") (pinfunction "XTAL2_56") (pintype "bidirectional"))
      (node (ref "Y1") (pin "1") (pinfunction "1_1") (pintype "passive"))
    )
    (net (code "47") (name "PITCH") (class "Default")
      (node (ref "J3") (pin "V") (pinfunction "V_V") (pintype "bidirectional"))
      (node (ref "J8") (pin "V") (pinfunction "V_V") (pintype "bidirectional"))
      (node (ref "U4") (pin "2") (pinfunction "PF3(ADC3/DIG4)_2") (pintype "bidirectional"))
    )
    (net (code "48") (name "RESET") (class "Default")
      (node (ref "B1") (pin "1") (pinfunction "1_1") (pintype "passive"))
      (node (ref "B1") (pin "2") (pinfunction "1_2") (pintype "passive"))
      (node (ref "C1") (pin "1") (pinfunction "1_1") (pintype "passive"))
      (node (ref "J4") (pin "5") (pinfunction "5_5") (pintype "passive"))
      (node (ref "R2") (pin "1") (pinfunction "1_1") (pintype "passive"))
      (node (ref "U4") (pin "12") (pinfunction "RSTN_12") (pintype "bidirectional"))
    )
    (net (code "49") (name "RF") (class "Default")
      (node (ref "D4") (pin "A1") (pinfunction "A1_A1") (pintype "passive"))
      (node (ref "U4") (pin "16") (pinfunction "PG2(AMR)_16") (pintype "bidirectional"))
    )
    (net (code "50") (name "ROLL") (class "Default")
      (node (ref "J3") (pin "H") (pinfunction "H_H") (pintype "bidirectional"))
      (node (ref "J8") (pin "H") (pinfunction "H_H") (pintype "bidirectional"))
      (node (ref "U4") (pin "1") (pinfunction "PF2(ADC2/DIG2)_1") (pintype "bidirectional"))
    )
    (net (code "51") (name "RXI") (class "Default")
      (node (ref "U3") (pin "5") (pinfunction "RXD_5") (pintype "input"))
      (node (ref "U5") (pin "10") (pinfunction "3Z_10") (pintype "bidirectional"))
    )
    (net (code "52") (name "RXI-0") (class "Default")
      (node (ref "U4") (pin "47") (pinfunction "PE1(TXD0)_47") (pintype "bidirectional"))
      (node (ref "U5") (pin "11") (pinfunction "3Y0_11") (pintype "bidirectional"))
    )
    (net (code "53") (name "RXI-1") (class "Default")
      (node (ref "JP1") (pin "RXI") (pinfunction "2_RXI") (pintype "passive"))
      (node (ref "U5") (pin "9") (pinfunction "3Y1_9") (pintype "bidirectional"))
    )
    (net (code "54") (name "RXLED") (class "Default")
      (node (ref "D5") (pin "C2") (pinfunction "C2_C2") (pintype "passive"))
      (node (ref "U3") (pin "22") (pinfunction "RXLED_22") (pintype "input"))
    )
    (net (code "55") (name "SCK") (class "Default")
      (node (ref "J4") (pin "3") (pinfunction "3_3") (pintype "passive"))
      (node (ref "U4") (pin "37") (pinfunction "PB1(SCK/PCINT1)_37") (pintype "bidirectional"))
    )
    (net (code "56") (name "SHIELD") (class "Default")
      (node (ref "B12") (pin "P2") (pinfunction "P2_P2") (pintype "bidirectional"))
    )
    (net (code "57") (name "THROTTLE") (class "Default")
      (node (ref "J2") (pin "V") (pinfunction "V_V") (pintype "bidirectional"))
      (node (ref "J7") (pin "V") (pinfunction "V_V") (pintype "bidirectional"))
      (node (ref "U4") (pin "64") (pinfunction "PF1(ADC1)_64") (pintype "bidirectional"))
    )
    (net (code "58") (name "TXLED") (class "Default")
      (node (ref "D5") (pin "C1") (pinfunction "C1_C1") (pintype "passive"))
      (node (ref "U3") (pin "23") (pinfunction "TXLED_23") (pintype "input"))
    )
    (net (code "59") (name "TXO") (class "Default")
      (node (ref "U3") (pin "1") (pinfunction "TXD_1") (pintype "output"))
      (node (ref "U5") (pin "6") (pinfunction "2Z_6") (pintype "bidirectional"))
    )
    (net (code "60") (name "TXO-0") (class "Default")
      (node (ref "U4") (pin "46") (pinfunction "PE0(RXD0/PCINT8)_46") (pintype "bidirectional"))
      (node (ref "U5") (pin "7") (pinfunction "2Y0_7") (pintype "bidirectional"))
    )
    (net (code "61") (name "TXO-1") (class "Default")
      (node (ref "JP1") (pin "TXO") (pinfunction "3_TXO") (pintype "passive"))
      (node (ref "U5") (pin "5") (pinfunction "2Y1_5") (pintype "bidirectional"))
    )
    (net (code "62") (name "USB_D_N") (class "Default")
      (node (ref "J1") (pin "2") (pinfunction "2-D-_2") (pintype "bidirectional"))
      (node (ref "U3") (pin "16") (pinfunction "USBDM_16") (pintype "bidirectional"))
    )
    (net (code "63") (name "USB_D_P") (class "Default")
      (node (ref "J1") (pin "3") (pinfunction "3-D+_3") (pintype "bidirectional"))
      (node (ref "U3") (pin "15") (pinfunction "USBDP_15") (pintype "bidirectional"))
    )
    (net (code "64") (name "VBAT") (class "Default")
      (node (ref "D2") (pin "C") (pinfunction "C_C") (pintype "passive"))
      (node (ref "D3") (pin "C") (pinfunction "C_C") (pintype "passive"))
      (node (ref "P2") (pin "T") (pinfunction "T_T") (pintype "bidirectional"))
      (node (ref "S1") (pin "2") (pinfunction "C_2") (pintype "bidirectional"))
      (node (ref "V10") (pin "P1") (pinfunction "N_P1") (pintype "bidirectional"))
    )
    (net (code "65") (name "VBUS") (class "Default")
      (node (ref "C5") (pin "1") (pinfunction "1_1") (pintype "passive"))
      (node (ref "D1") (pin "A2") (pinfunction "A2_A2") (pintype "passive"))
      (node (ref "D2") (pin "A") (pinfunction "A_A") (pintype "passive"))
      (node (ref "J1") (pin "1") (pinfunction "1-VCC_1") (pintype "bidirectional"))
      (node (ref "P1") (pin "T") (pinfunction "T_T") (pintype "bidirectional"))
      (node (ref "U2") (pin "4") (pinfunction "VDD_4") (pintype "power_in"))
      (node (ref "V1") (pin "P1") (pinfunction "N_P1") (pintype "bidirectional"))
      (node (ref "V2") (pin "P1") (pinfunction "N_P1") (pintype "bidirectional"))
      (node (ref "V23") (pin "P1") (pinfunction "N_P1") (pintype "bidirectional"))
      (node (ref "V24") (pin "P1") (pinfunction "N_P1") (pintype "bidirectional"))
      (node (ref "V26") (pin "P1") (pinfunction "N_P1") (pintype "bidirectional"))
      (node (ref "V27") (pin "P1") (pinfunction "N_P1") (pintype "bidirectional"))
      (node (ref "V28") (pin "P1") (pinfunction "N_P1") (pintype "bidirectional"))
    )
    (net (code "66") (name "VREG_IN") (class "Default")
      (node (ref "C7") (pin "1") (pinfunction "1_1") (pintype "passive"))
      (node (ref "C8") (pin "1") (pinfunction "1_1") (pintype "passive"))
      (node (ref "L1") (pin "RAW") (pinfunction "VIN_RAW") (pintype "bidirectional"))
      (node (ref "S1") (pin "1") (pinfunction "ON_1") (pintype "bidirectional"))
      (node (ref "U3") (pin "20") (pinfunction "VCC_20") (pintype "power_in"))
    )
    (net (code "67") (name "YAW") (class "Default")
      (node (ref "J2") (pin "H") (pinfunction "H_H") (pintype "bidirectional"))
      (node (ref "J7") (pin "H") (pinfunction "H_H") (pintype "bidirectional"))
      (node (ref "U4") (pin "63") (pinfunction "PF0(ADC0)_63") (pintype "bidirectional"))
    )
    (net (code "68") (name "unconnected-(J1-4-ID-Pad4)") (class "Default")
      (node (ref "J1") (pin "4") (pinfunction "4-ID_4") (pintype "bidirectional"))
    )
    (net (code "69") (name "unconnected-(L1-PadSCK)") (class "Default")
      (node (ref "L1") (pin "SCK") (pinfunction "SCK_SCK") (pintype "bidirectional"))
    )
    (net (code "70") (name "unconnected-(L1-PadSDI)") (class "Default")
      (node (ref "L1") (pin "SDI") (pinfunction "SDI_SDI") (pintype "bidirectional"))
    )
    (net (code "71") (name "unconnected-(L1-PadSDO)") (class "Default")
      (node (ref "L1") (pin "SDO") (pinfunction "SDO_SDO") (pintype "bidirectional"))
    )
    (net (code "72") (name "unconnected-(L1-Pad{slash}CS)") (class "Default")
      (node (ref "L1") (pin "/CS") (pinfunction "/CS_/CS") (pintype "bidirectional"))
    )
    (net (code "73") (name "unconnected-(L1-SCL-PadCL)") (class "Default")
      (node (ref "L1") (pin "CL") (pinfunction "SCL_CL") (pintype "bidirectional"))
    )
    (net (code "74") (name "unconnected-(L1-SDA-PadDA)") (class "Default")
      (node (ref "L1") (pin "DA") (pinfunction "SDA_DA") (pintype "bidirectional"))
    )
    (net (code "75") (name "unconnected-(S1-OFF-Pad3)") (class "Default")
      (node (ref "S1") (pin "3") (pinfunction "OFF_3") (pintype "bidirectional"))
    )
    (net (code "76") (name "unconnected-(U3-DCD-Pad10)") (class "Default")
      (node (ref "U3") (pin "10") (pinfunction "DCD_10") (pintype "input"))
    )
    (net (code "77") (name "unconnected-(U3-DSR-Pad9)") (class "Default")
      (node (ref "U3") (pin "9") (pinfunction "DSR_9") (pintype "input"))
    )
    (net (code "78") (name "unconnected-(U3-OSCI-Pad27)") (class "Default")
      (node (ref "U3") (pin "27") (pinfunction "OSCI_27") (pintype "input"))
    )
    (net (code "79") (name "unconnected-(U3-OSCO-Pad28)") (class "Default")
      (node (ref "U3") (pin "28") (pinfunction "OSCO_28") (pintype "output"))
    )
    (net (code "80") (name "unconnected-(U3-PWREN-Pad14)") (class "Default")
      (node (ref "U3") (pin "14") (pinfunction "PWREN_14") (pintype "input"))
    )
    (net (code "81") (name "unconnected-(U3-RESET-Pad19)") (class "Default")
      (node (ref "U3") (pin "19") (pinfunction "RESET_19") (pintype "input"))
    )
    (net (code "82") (name "unconnected-(U3-RI-Pad6)") (class "Default")
      (node (ref "U3") (pin "6") (pinfunction "RI_6") (pintype "input"))
    )
    (net (code "83") (name "unconnected-(U3-RTS-Pad3)") (class "Default")
      (node (ref "U3") (pin "3") (pinfunction "RTS_3") (pintype "output"))
    )
    (net (code "84") (name "unconnected-(U3-SLEEP-Pad12)") (class "Default")
      (node (ref "U3") (pin "12") (pinfunction "SLEEP_12") (pintype "input"))
    )
    (net (code "85") (name "unconnected-(U3-TXDEN-Pad13)") (class "Default")
      (node (ref "U3") (pin "13") (pinfunction "TXDEN_13") (pintype "input"))
    )
    (net (code "86") (name "unconnected-(U4-AREF-Pad62)") (class "Default")
      (node (ref "U4") (pin "62") (pinfunction "AREF_62") (pintype "bidirectional"))
    )
    (net (code "87") (name "unconnected-(U4-PB0(SSN{slash}PCINT0)-Pad36)") (class "Default")
      (node (ref "U4") (pin "36") (pinfunction "PB0(SSN/PCINT0)_36") (pintype "bidirectional"))
    )
    (net (code "88") (name "unconnected-(U4-PB6(OC1B{slash}PCINT6)-Pad42)") (class "Default")
      (node (ref "U4") (pin "42") (pinfunction "PB6(OC1B/PCINT6)_42") (pintype "bidirectional"))
    )
    (net (code "89") (name "unconnected-(U4-PB7(OC0A{slash}OC1C{slash}PCINT7)-Pad43)") (class "Default")
      (node (ref "U4") (pin "43") (pinfunction "PB7(OC0A/OC1C/PCINT7)_43") (pintype "bidirectional"))
    )
    (net (code "90") (name "unconnected-(U4-PD4(ICP1)-Pad29)") (class "Default")
      (node (ref "U4") (pin "29") (pinfunction "PD4(ICP1)_29") (pintype "bidirectional"))
    )
    (net (code "91") (name "unconnected-(U4-PD5(XCK1)-Pad30)") (class "Default")
      (node (ref "U4") (pin "30") (pinfunction "PD5(XCK1)_30") (pintype "bidirectional"))
    )
    (net (code "92") (name "unconnected-(U4-PE2(XCK0{slash}AIN0)-Pad48)") (class "Default")
      (node (ref "U4") (pin "48") (pinfunction "PE2(XCK0/AIN0)_48") (pintype "bidirectional"))
    )
    (net (code "93") (name "unconnected-(U4-PE3(OC3A{slash}AIN1)-Pad49)") (class "Default")
      (node (ref "U4") (pin "49") (pinfunction "PE3(OC3A/AIN1)_49") (pintype "bidirectional"))
    )
    (net (code "94") (name "unconnected-(U4-PF5(ADC5{slash}TMS)-Pad4)") (class "Default")
      (node (ref "U4") (pin "4") (pinfunction "PF5(ADC5/TMS)_4") (pintype "bidirectional"))
    )
    (net (code "95") (name "unconnected-(U4-PF6(ADC6{slash}TDO)-Pad5)") (class "Default")
      (node (ref "U4") (pin "5") (pinfunction "PF6(ADC6/TDO)_5") (pintype "bidirectional"))
    )
    (net (code "96") (name "unconnected-(U4-PF7(ADC7{slash}TDI)-Pad6)") (class "Default")
      (node (ref "U4") (pin "6") (pinfunction "PF7(ADC7/TDI)_6") (pintype "bidirectional"))
    )
    (net (code "97") (name "unconnected-(U4-PG3(TOSC2)-Pad17)") (class "Default")
      (node (ref "U4") (pin "17") (pinfunction "PG3(TOSC2)_17") (pintype "bidirectional"))
    )
    (net (code "98") (name "unconnected-(U4-PG4(TOSC1)-Pad18)") (class "Default")
      (node (ref "U4") (pin "18") (pinfunction "PG4(TOSC1)_18") (pintype "bidirectional"))
    )
    (net (code "99") (name "unconnected-(U4-PG5(OC0B)-Pad19)") (class "Default")
      (node (ref "U4") (pin "19") (pinfunction "PG5(OC0B)_19") (pintype "bidirectional"))
    )
    (net (code "100") (name "unconnected-(U4-RSTON-Pad13)") (class "Default")
      (node (ref "U4") (pin "13") (pinfunction "RSTON_13") (pintype "bidirectional"))
    )
  )
)
